# batt_switch.net
KiCad netlist of a schematic drawn in Altium Designer
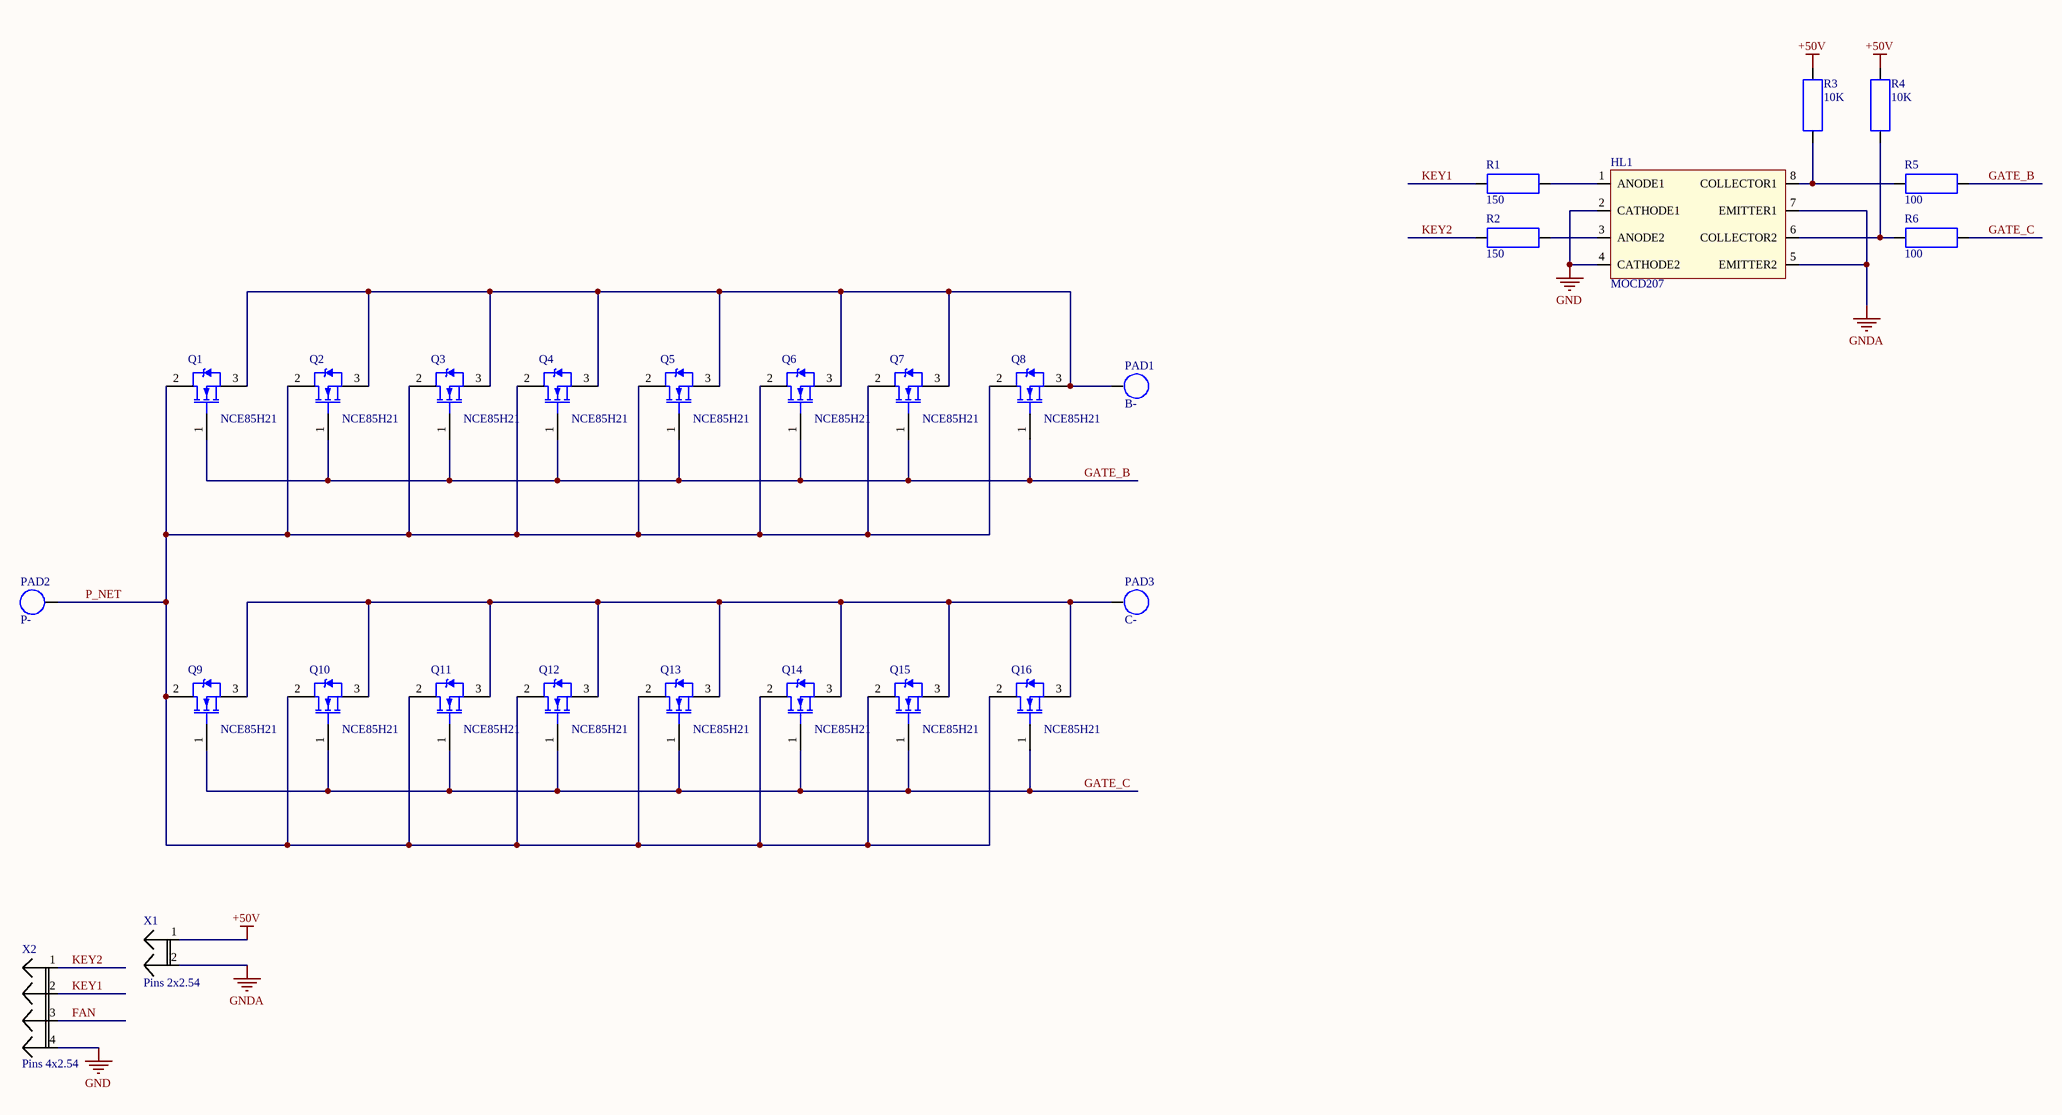
[diagram p0: batt_switch.SchDoc]

(export (version "E")
  (design (tool "Eeschema 10.0.6"))
  (components
    (comp (ref "HL1")
      (value "MOCD207")
      (footprint "A_H_pcb_lib:SO8")
      (libsource (lib "A_H_sch_lib") (part "Optopara_MOCD207"))
    )
    (comp (ref "PAD1") (value "B-") (footprint "PAD") (libsource (lib "A_H_sch_lib") (part "PAD")))
    (comp (ref "PAD2") (value "P-") (footprint "PAD") (libsource (lib "A_H_sch_lib") (part "PAD")))
    (comp (ref "PAD3") (value "C-") (footprint "PAD") (libsource (lib "A_H_sch_lib") (part "PAD")))
    (comp (ref "Q1")
      (value "NCE85H21")
      (footprint "A_H_pcb_lib:NCE85H21")
      (libsource (lib "A_H_sch_lib") (part "NCE85H21"))
    )
    (comp (ref "Q2")
      (value "NCE85H21")
      (footprint "A_H_pcb_lib:NCE85H21")
      (libsource (lib "A_H_sch_lib") (part "NCE85H21"))
    )
    (comp (ref "Q3")
      (value "NCE85H21")
      (footprint "A_H_pcb_lib:NCE85H21")
      (libsource (lib "A_H_sch_lib") (part "NCE85H21"))
    )
    (comp (ref "Q4")
      (value "NCE85H21")
      (footprint "A_H_pcb_lib:NCE85H21")
      (libsource (lib "A_H_sch_lib") (part "NCE85H21"))
    )
    (comp (ref "Q5")
      (value "NCE85H21")
      (footprint "A_H_pcb_lib:NCE85H21")
      (libsource (lib "A_H_sch_lib") (part "NCE85H21"))
    )
    (comp (ref "Q6")
      (value "NCE85H21")
      (footprint "A_H_pcb_lib:NCE85H21")
      (libsource (lib "A_H_sch_lib") (part "NCE85H21"))
    )
    (comp (ref "Q7")
      (value "NCE85H21")
      (footprint "A_H_pcb_lib:NCE85H21")
      (libsource (lib "A_H_sch_lib") (part "NCE85H21"))
    )
    (comp (ref "Q8")
      (value "NCE85H21")
      (footprint "A_H_pcb_lib:NCE85H21")
      (libsource (lib "A_H_sch_lib") (part "NCE85H21"))
    )
    (comp (ref "Q9")
      (value "NCE85H21")
      (footprint "A_H_pcb_lib:NCE85H21")
      (libsource (lib "A_H_sch_lib") (part "NCE85H21"))
    )
    (comp (ref "Q10")
      (value "NCE85H21")
      (footprint "A_H_pcb_lib:NCE85H21")
      (libsource (lib "A_H_sch_lib") (part "NCE85H21"))
    )
    (comp (ref "Q11")
      (value "NCE85H21")
      (footprint "A_H_pcb_lib:NCE85H21")
      (libsource (lib "A_H_sch_lib") (part "NCE85H21"))
    )
    (comp (ref "Q12")
      (value "NCE85H21")
      (footprint "A_H_pcb_lib:NCE85H21")
      (libsource (lib "A_H_sch_lib") (part "NCE85H21"))
    )
    (comp (ref "Q13")
      (value "NCE85H21")
      (footprint "A_H_pcb_lib:NCE85H21")
      (libsource (lib "A_H_sch_lib") (part "NCE85H21"))
    )
    (comp (ref "Q14")
      (value "NCE85H21")
      (footprint "A_H_pcb_lib:NCE85H21")
      (libsource (lib "A_H_sch_lib") (part "NCE85H21"))
    )
    (comp (ref "Q15")
      (value "NCE85H21")
      (footprint "A_H_pcb_lib:NCE85H21")
      (libsource (lib "A_H_sch_lib") (part "NCE85H21"))
    )
    (comp (ref "Q16")
      (value "NCE85H21")
      (footprint "A_H_pcb_lib:NCE85H21")
      (libsource (lib "A_H_sch_lib") (part "NCE85H21"))
    )
    (comp (ref "R1") (value "150") (footprint "R0805") (libsource (lib "A_H_sch_lib") (part "Resistor")))
    (comp (ref "R2") (value "150") (footprint "R0805") (libsource (lib "A_H_sch_lib") (part "Resistor")))
    (comp (ref "R3") (value "10K") (footprint "R0805") (libsource (lib "A_H_sch_lib") (part "Resistor")))
    (comp (ref "R4") (value "10K") (footprint "R0805") (libsource (lib "A_H_sch_lib") (part "Resistor")))
    (comp (ref "R5") (value "100") (footprint "R0805") (libsource (lib "A_H_sch_lib") (part "Resistor")))
    (comp (ref "R6") (value "100") (footprint "R0805") (libsource (lib "A_H_sch_lib") (part "Resistor")))
    (comp (ref "X1")
      (value "Pins 2x2.54")
      (footprint "Pins 2x2.54")
      (libsource (lib "A_H_sch_lib") (part "Pins 2x2.54"))
    )
    (comp (ref "X2")
      (value "Pins 4x2.54")
      (footprint "Pins 4x2.54")
      (libsource (lib "A_H_sch_lib") (part "Pins 4x2.54"))
    )
  )
  (nets
    (net (code "1") (name "+50V") (class "Default")
      (node (ref "R3") (pin "2") (pinfunction "2_2") (pintype "passive"))
      (node (ref "R4") (pin "2") (pinfunction "2_2") (pintype "passive"))
      (node (ref "X1") (pin "1") (pinfunction "1_1") (pintype "passive"))
    )
    (net (code "2") (name "/FAN") (class "Default")
      (node (ref "X2") (pin "3") (pinfunction "3_3") (pintype "passive"))
    )
    (net (code "3") (name "/GATE_B") (class "Default")
      (node (ref "Q1") (pin "1") (pinfunction "G_1") (pintype "passive"))
      (node (ref "Q2") (pin "1") (pinfunction "G_1") (pintype "passive"))
      (node (ref "Q3") (pin "1") (pinfunction "G_1") (pintype "passive"))
      (node (ref "Q4") (pin "1") (pinfunction "G_1") (pintype "passive"))
      (node (ref "Q5") (pin "1") (pinfunction "G_1") (pintype "passive"))
      (node (ref "Q6") (pin "1") (pinfunction "G_1") (pintype "passive"))
      (node (ref "Q7") (pin "1") (pinfunction "G_1") (pintype "passive"))
      (node (ref "Q8") (pin "1") (pinfunction "G_1") (pintype "passive"))
      (node (ref "R5") (pin "2") (pinfunction "2_2") (pintype "passive"))
    )
    (net (code "4") (name "/GATE_C") (class "Default")
      (node (ref "Q10") (pin "1") (pinfunction "G_1") (pintype "passive"))
      (node (ref "Q11") (pin "1") (pinfunction "G_1") (pintype "passive"))
      (node (ref "Q12") (pin "1") (pinfunction "G_1") (pintype "passive"))
      (node (ref "Q13") (pin "1") (pinfunction "G_1") (pintype "passive"))
      (node (ref "Q14") (pin "1") (pinfunction "G_1") (pintype "passive"))
      (node (ref "Q15") (pin "1") (pinfunction "G_1") (pintype "passive"))
      (node (ref "Q16") (pin "1") (pinfunction "G_1") (pintype "passive"))
      (node (ref "Q9") (pin "1") (pinfunction "G_1") (pintype "passive"))
      (node (ref "R6") (pin "2") (pinfunction "2_2") (pintype "passive"))
    )
    (net (code "5") (name "/KEY1") (class "Default")
      (node (ref "R1") (pin "1") (pinfunction "1_1") (pintype "passive"))
      (node (ref "X2") (pin "2") (pinfunction "2_2") (pintype "passive"))
    )
    (net (code "6") (name "/KEY2") (class "Default")
      (node (ref "R2") (pin "1") (pinfunction "1_1") (pintype "passive"))
      (node (ref "X2") (pin "1") (pinfunction "1_1") (pintype "passive"))
    )
    (net (code "7") (name "/P_NET") (class "Default")
      (node (ref "PAD2") (pin "1") (pinfunction "1_1") (pintype "passive"))
      (node (ref "Q1") (pin "2") (pinfunction "D_2") (pintype "passive"))
      (node (ref "Q10") (pin "2") (pinfunction "D_2") (pintype "passive"))
      (node (ref "Q11") (pin "2") (pinfunction "D_2") (pintype "passive"))
      (node (ref "Q12") (pin "2") (pinfunction "D_2") (pintype "passive"))
      (node (ref "Q13") (pin "2") (pinfunction "D_2") (pintype "passive"))
      (node (ref "Q14") (pin "2") (pinfunction "D_2") (pintype "passive"))
      (node (ref "Q15") (pin "2") (pinfunction "D_2") (pintype "passive"))
      (node (ref "Q16") (pin "2") (pinfunction "D_2") (pintype "passive"))
      (node (ref "Q2") (pin "2") (pinfunction "D_2") (pintype "passive"))
      (node (ref "Q3") (pin "2") (pinfunction "D_2") (pintype "passive"))
      (node (ref "Q4") (pin "2") (pinfunction "D_2") (pintype "passive"))
      (node (ref "Q5") (pin "2") (pinfunction "D_2") (pintype "passive"))
      (node (ref "Q6") (pin "2") (pinfunction "D_2") (pintype "passive"))
      (node (ref "Q7") (pin "2") (pinfunction "D_2") (pintype "passive"))
      (node (ref "Q8") (pin "2") (pinfunction "D_2") (pintype "passive"))
      (node (ref "Q9") (pin "2") (pinfunction "D_2") (pintype "passive"))
    )
    (net (code "8") (name "GND") (class "Default")
      (node (ref "HL1") (pin "2") (pinfunction "CATHODE1_2") (pintype "passive"))
      (node (ref "HL1") (pin "4") (pinfunction "CATHODE2_4") (pintype "passive"))
      (node (ref "X2") (pin "4") (pinfunction "4_4") (pintype "passive"))
    )
    (net (code "9") (name "GNDA") (class "Default")
      (node (ref "HL1") (pin "5") (pinfunction "EMITTER2_5") (pintype "passive"))
      (node (ref "HL1") (pin "7") (pinfunction "EMITTER1_7") (pintype "passive"))
      (node (ref "X1") (pin "2") (pinfunction "2_2") (pintype "passive"))
    )
    (net (code "10") (name "Net-(HL1-ANODE1)") (class "Default")
      (node (ref "HL1") (pin "1") (pinfunction "ANODE1_1") (pintype "passive"))
      (node (ref "R1") (pin "2") (pinfunction "2_2") (pintype "passive"))
    )
    (net (code "11") (name "Net-(HL1-ANODE2)") (class "Default")
      (node (ref "HL1") (pin "3") (pinfunction "ANODE2_3") (pintype "passive"))
      (node (ref "R2") (pin "2") (pinfunction "2_2") (pintype "passive"))
    )
    (net (code "12") (name "Net-(HL1-COLLECTOR1)") (class "Default")
      (node (ref "HL1") (pin "8") (pinfunction "COLLECTOR1_8") (pintype "passive"))
      (node (ref "R3") (pin "1") (pinfunction "1_1") (pintype "passive"))
      (node (ref "R5") (pin "1") (pinfunction "1_1") (pintype "passive"))
    )
    (net (code "13") (name "Net-(HL1-COLLECTOR2)") (class "Default")
      (node (ref "HL1") (pin "6") (pinfunction "COLLECTOR2_6") (pintype "passive"))
      (node (ref "R4") (pin "1") (pinfunction "1_1") (pintype "passive"))
      (node (ref "R6") (pin "1") (pinfunction "1_1") (pintype "passive"))
    )
    (net (code "14") (name "Net-(Q1-S)") (class "Default")
      (node (ref "PAD1") (pin "1") (pinfunction "1_1") (pintype "passive"))
      (node (ref "Q1") (pin "3") (pinfunction "S_3") (pintype "passive"))
      (node (ref "Q2") (pin "3") (pinfunction "S_3") (pintype "passive"))
      (node (ref "Q3") (pin "3") (pinfunction "S_3") (pintype "passive"))
      (node (ref "Q4") (pin "3") (pinfunction "S_3") (pintype "passive"))
      (node (ref "Q5") (pin "3") (pinfunction "S_3") (pintype "passive"))
      (node (ref "Q6") (pin "3") (pinfunction "S_3") (pintype "passive"))
      (node (ref "Q7") (pin "3") (pinfunction "S_3") (pintype "passive"))
      (node (ref "Q8") (pin "3") (pinfunction "S_3") (pintype "passive"))
    )
    (net (code "15") (name "Net-(Q10-S)") (class "Default")
      (node (ref "PAD3") (pin "1") (pinfunction "1_1") (pintype "passive"))
      (node (ref "Q10") (pin "3") (pinfunction "S_3") (pintype "passive"))
      (node (ref "Q11") (pin "3") (pinfunction "S_3") (pintype "passive"))
      (node (ref "Q12") (pin "3") (pinfunction "S_3") (pintype "passive"))
      (node (ref "Q13") (pin "3") (pinfunction "S_3") (pintype "passive"))
      (node (ref "Q14") (pin "3") (pinfunction "S_3") (pintype "passive"))
      (node (ref "Q15") (pin "3") (pinfunction "S_3") (pintype "passive"))
      (node (ref "Q16") (pin "3") (pinfunction "S_3") (pintype "passive"))
      (node (ref "Q9") (pin "3") (pinfunction "S_3") (pintype "passive"))
    )
  )
)
